# 03_CONNECTION.net
KiCad netlist of a schematic drawn in Altium Designer
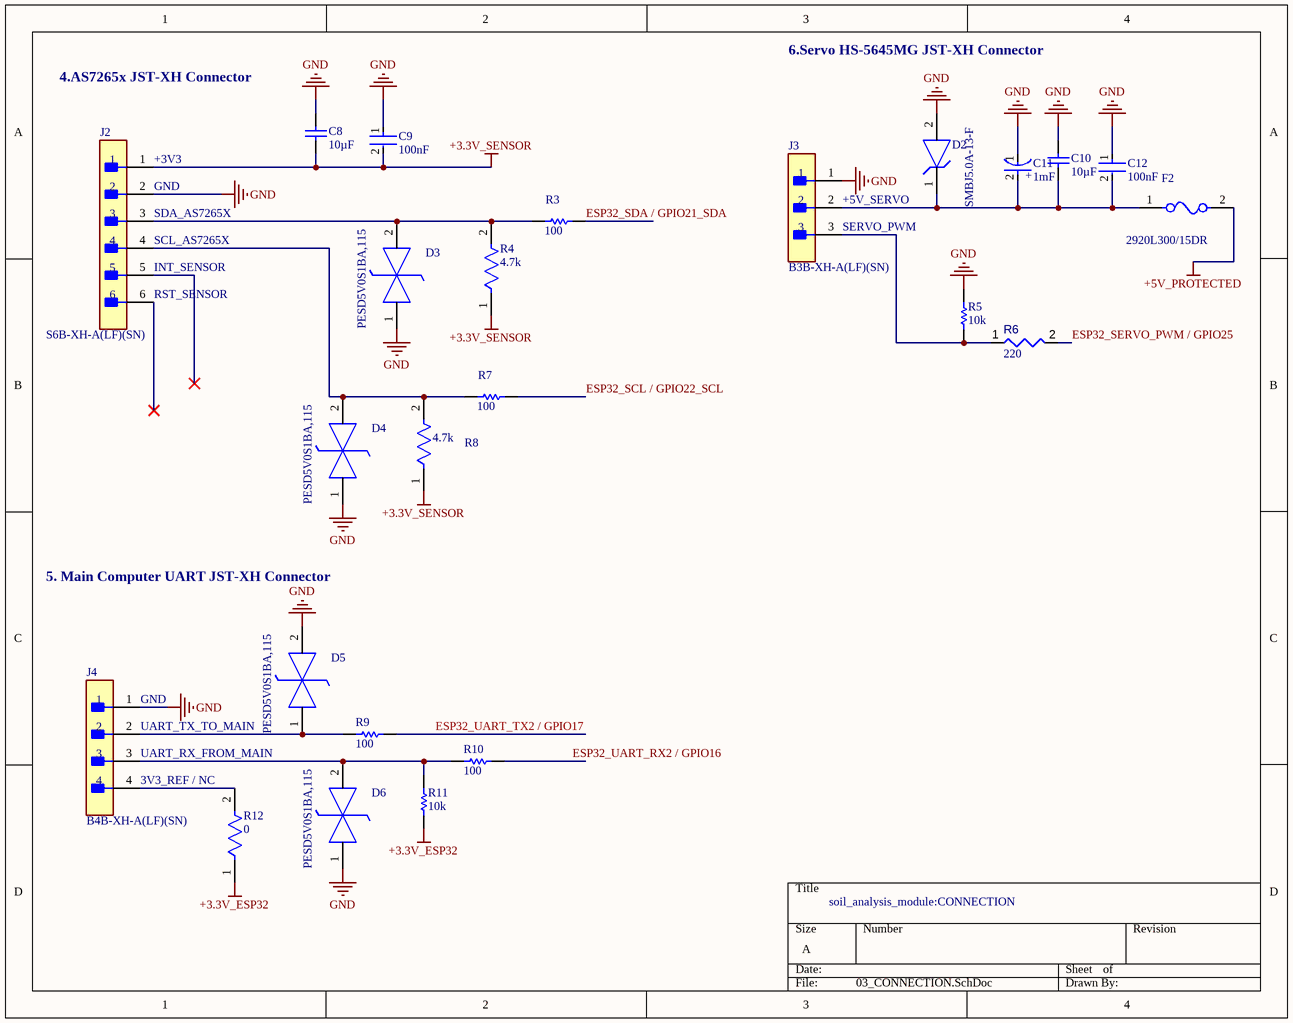
[diagram p0: 03_CONNECTION.SchDoc]

(export (version "E")
  (design (tool "Eeschema 10.0.6"))
  (components
    (comp (ref "C8")
      (value "10µF")
      (footprint "CAPC3216X180X55ML20T25")
      (description "16V 10uF X7R ±10% 1206 Multilayer Ceramic Capacitors MLCC - SMD/SMT ROHS")
      (fields (field (name "TOLERANCE") "10%") (field (name "Comment") "GRM31CR71C106KA12L"))
      (libsource (lib "Maksym Pleshyvtsev") (part "CAP-NP-2"))
    )
    (comp (ref "C9")
      (value "100nF")
      (footprint "FP-CC1206-1_25-MFG")
      (description "50V 100nF X7R ±10% 1206 Multilayer Ceramic Capacitors MLCC - SMD/SMT ROHS")
      (fields (field (name "TOLERANCE") "10%") (field (name "Comment") "CC1206KRX7R9BB104"))
      (libsource (lib "Maksym Pleshyvtsev") (part "11868f565c42a9108669ba33697ecf6"))
    )
    (comp (ref "C10")
      (value "10µF")
      (footprint "CAPC3216X180X55ML20T25")
      (description "16V 10uF X7R ±10% 1206 Multilayer Ceramic Capacitors MLCC - SMD/SMT ROHS")
      (fields (field (name "TOLERANCE") "10%") (field (name "Comment") "GRM31CR71C106KA12L"))
      (libsource (lib "Maksym Pleshyvtsev") (part "CAP-NP-2"))
    )
    (comp (ref "C11")
      (value "1mF")
      (footprint "FP-RAD-TH-D_8_0_5-L_15_1-MFG")
      (description "Aluminum Electrolytic Capacitor, 1000 uF, 10 V, ± 20%, 8000 hours @ 105°C, Radial Leaded")
      (fields (field (name "TOLERANCE") "20%") (field (name "Comment") "EEUFR1A102L"))
      (libsource (lib "Maksym Pleshyvtsev") (part "a00bbbee19879c290e62620ae7e47b1"))
    )
    (comp (ref "C12")
      (value "100nF")
      (footprint "FP-CC1206-1_25-MFG")
      (description "50V 100nF X7R ±10% 1206 Multilayer Ceramic Capacitors MLCC - SMD/SMT ROHS")
      (fields (field (name "TOLERANCE") "10%") (field (name "Comment") "CC1206KRX7R9BB104"))
      (libsource (lib "Maksym Pleshyvtsev") (part "11868f565c42a9108669ba33697ecf6"))
    )
    (comp (ref "D2")
      (value "SMBJ5.0A-13-F")
      (footprint "FP-SMB-MFG")
      (description "SMBJ5.0A Series 600 W 5.0 V Surface Mount Uni-Directional TVS Diode - DO-214AA")
      (libsource (lib "Maksym Pleshyvtsev") (part "673ecd2ea4d7fb87b4005b0cb348b7d"))
    )
    (comp (ref "D3")
      (value "PESD5V0S1BA,115")
      (footprint "PESD5V0S1BA,115-Footprint-1")
      (description "Tvs Diodes & Esd Suppressors; PESD5V0S1BA, 115; Nexperia; 5 V; 2; 14 V; 5.5 V")
      (libsource (lib "Maksym Pleshyvtsev") (part "PESD5V0S1BA,115-Symbol-1"))
    )
    (comp (ref "D4")
      (value "PESD5V0S1BA,115")
      (footprint "PESD5V0S1BA,115-Footprint-1")
      (description "Tvs Diodes & Esd Suppressors; PESD5V0S1BA, 115; Nexperia; 5 V; 2; 14 V; 5.5 V")
      (libsource (lib "Maksym Pleshyvtsev") (part "PESD5V0S1BA,115-Symbol-1"))
    )
    (comp (ref "D5")
      (value "PESD5V0S1BA,115")
      (footprint "PESD5V0S1BA,115-Footprint-1")
      (description "Tvs Diodes & Esd Suppressors; PESD5V0S1BA, 115; Nexperia; 5 V; 2; 14 V; 5.5 V")
      (libsource (lib "Maksym Pleshyvtsev") (part "PESD5V0S1BA,115-Symbol-1"))
    )
    (comp (ref "D6")
      (value "PESD5V0S1BA,115")
      (footprint "PESD5V0S1BA,115-Footprint-1")
      (description "Tvs Diodes & Esd Suppressors; PESD5V0S1BA, 115; Nexperia; 5 V; 2; 14 V; 5.5 V")
      (libsource (lib "Maksym Pleshyvtsev") (part "PESD5V0S1BA,115-Symbol-1"))
    )
    (comp (ref "F2")
      (value "2920L300/15DR")
      (footprint "FP-2920L-MFG")
      (description "PTC Resettable Fuses; 2920L300/15DR; LITTELFUSE; 5 A; 3 A; 20 s; 2920")
      (libsource (lib "Maksym Pleshyvtsev") (part "5bcf9b9f640e542cf0359d10258e979"))
    )
    (comp (ref "J2")
      (value "S6B-XH-A(LF)(SN)")
      (footprint "FP-S6B-XH-A_LF_SN-MFG")
      (description "Board Connector, 6 Contact(s), 1 Row(s), Male, Right Angle, Solder Terminal, ROHS COMPLIANT")
      (libsource (lib "Maksym Pleshyvtsev") (part "f2cb566baf1c37ab5a3b8e90bbeafd6"))
    )
    (comp (ref "J3")
      (value "B3B-XH-A(LF)(SN)")
      (footprint "FP-B3B-XH-A_LF_SN-MFG")
      (description "Connector Header, XH Series, 3 Position, 2.50mm, Through Hole, Press-Fit, Solder, Natural")
      (libsource (lib "Maksym Pleshyvtsev") (part "0d3f023dd272f625e17a2be33dea85f"))
    )
    (comp (ref "J4")
      (value "B4B-XH-A(LF)(SN)")
      (footprint "FP-B4B-XH-A_LF_SN-MFG")
      (description "Connector Header, 4 Positions, 2.50mm, Solder, Detent Lock, Natural")
      (libsource (lib "Maksym Pleshyvtsev") (part "299a8cea1bdcbc3624fe62c390fa72c"))
    )
    (comp (ref "R3")
      (value "100")
      (footprint "RESC3116X65X40LL10T20")
      (description "Res Thick Film 1206 100 Ohm 1% 0.25W(1/4W) ±100ppm/C Pad SMD T/R")
      (fields (field (name "TOLERANCE") "1%") (field (name "Comment") "RC1206FR-07100RL"))
      (libsource (lib "Maksym Pleshyvtsev") (part "RES-2"))
    )
    (comp (ref "R4")
      (value "4.7k")
      (footprint "FP-RC1206-0_65-MFG")
      (description "Res Thick Film 1206 4.7K Ohm 1% 0.25W(1/4W) ±100ppm/C Pad SMD T/R")
      (fields (field (name "TOLERANCE") "1%") (field (name "Comment") "RC1206FR-074K7L"))
      (libsource (lib "Maksym Pleshyvtsev") (part "1029c3af85768c4190bb7ad29bc67b5"))
    )
    (comp (ref "R5")
      (value "10k")
      (footprint "RESC3116X65X40ML10T20")
      (description "250Mw Thick Film Resistors 100Ppm/ 1% 10K 1206 Chip Resistor Surface Mount Rohs")
      (fields (field (name "TOLERANCE") "1%") (field (name "Comment") "RC1206FR-0710KL"))
      (libsource (lib "Maksym Pleshyvtsev") (part "RES-2"))
    )
    (comp (ref "R6")
      (value "220")
      (footprint "RC1206FR-07220RL-Footprint-1")
      (description "250mW Thick Film Resistors 200V ±100ppm/℃ ±1% 220Ω 1206 Chip Resistor - Surface Mount ROHS")
      (fields (field (name "TOLERANCE") "1%") (field (name "Comment") "RC1206FR-07220RL"))
      (libsource (lib "") (part "RES-2_1"))
    )
    (comp (ref "R7")
      (value "100")
      (footprint "RESC3116X65X40LL10T20")
      (description "Res Thick Film 1206 100 Ohm 1% 0.25W(1/4W) ±100ppm/C Pad SMD T/R")
      (fields (field (name "TOLERANCE") "1%") (field (name "Comment") "RC1206FR-07100RL"))
      (libsource (lib "Maksym Pleshyvtsev") (part "RES-2"))
    )
    (comp (ref "R8")
      (value "4.7k")
      (footprint "FP-RC1206-0_65-MFG")
      (description "Res Thick Film 1206 4.7K Ohm 1% 0.25W(1/4W) ±100ppm/C Pad SMD T/R")
      (fields (field (name "TOLERANCE") "1%") (field (name "Comment") "RC1206FR-074K7L"))
      (libsource (lib "Maksym Pleshyvtsev") (part "1029c3af85768c4190bb7ad29bc67b5"))
    )
    (comp (ref "R9")
      (value "100")
      (footprint "RESC3116X65X40LL10T20")
      (description "Res Thick Film 1206 100 Ohm 1% 0.25W(1/4W) ±100ppm/C Pad SMD T/R")
      (fields (field (name "TOLERANCE") "1%") (field (name "Comment") "RC1206FR-07100RL"))
      (libsource (lib "Maksym Pleshyvtsev") (part "RES-2"))
    )
    (comp (ref "R10")
      (value "100")
      (footprint "RESC3116X65X40LL10T20")
      (description "Res Thick Film 1206 100 Ohm 1% 0.25W(1/4W) ±100ppm/C Pad SMD T/R")
      (fields (field (name "TOLERANCE") "1%") (field (name "Comment") "RC1206FR-07100RL"))
      (libsource (lib "Maksym Pleshyvtsev") (part "RES-2"))
    )
    (comp (ref "R11")
      (value "10k")
      (footprint "RESC3116X65X40ML10T20")
      (description "250Mw Thick Film Resistors 100Ppm/ 1% 10K 1206 Chip Resistor Surface Mount Rohs")
      (fields (field (name "TOLERANCE") "1%") (field (name "Comment") "RC1206FR-0710KL"))
      (libsource (lib "Maksym Pleshyvtsev") (part "RES-2"))
    )
    (comp (ref "R12")
      (value "0")
      (footprint "FP-RC1206-MFG")
      (description "GENERAL PURPOSE CHIP RESISTOR Metal Glaze/thick Film, 0.25W, 0ohm, Surface Mount, 1206")
      (fields (field (name "TOLERANCE") "5%") (field (name "Comment") "RC1206JR-070RL"))
      (libsource (lib "Maksym Pleshyvtsev") (part "1029c3af85768c4190bb7ad29bc67b5"))
    )
  )
  (nets
    (net (code "1") (name "+3.3V_ESP32") (class "Default")
      (node (ref "R11") (pin "1") (pinfunction "1_1") (pintype "passive"))
      (node (ref "R12") (pin "1") (pinfunction "1_1") (pintype "passive"))
    )
    (net (code "2") (name "+3.3V_SENSOR") (class "Default")
      (node (ref "C8") (pin "1") (pinfunction "1_1") (pintype "passive"))
      (node (ref "C9") (pin "2") (pinfunction "2_2") (pintype "passive"))
      (node (ref "J2") (pin "1") (pinfunction "1_1") (pintype "passive"))
      (node (ref "R4") (pin "1") (pinfunction "1_1") (pintype "passive"))
      (node (ref "R8") (pin "1") (pinfunction "1_1") (pintype "passive"))
    )
    (net (code "3") (name "+5V_PROTECTED") (class "Default")
      (node (ref "F2") (pin "2") (pinfunction "2_2") (pintype "passive"))
    )
    (net (code "4") (name "/ESP32_SCL {slash} GPIO22_SCL") (class "Default")
      (node (ref "R7") (pin "2") (pinfunction "2_2") (pintype "passive"))
    )
    (net (code "5") (name "/ESP32_SDA {slash} GPIO21_SDA") (class "Default")
      (node (ref "R3") (pin "2") (pinfunction "2_2") (pintype "passive"))
    )
    (net (code "6") (name "/ESP32_SERVO_PWM {slash} GPIO25") (class "Default")
      (node (ref "R6") (pin "2") (pinfunction "2_2") (pintype "passive"))
    )
    (net (code "7") (name "/ESP32_UART_RX2 {slash} GPIO16") (class "Default")
      (node (ref "R10") (pin "2") (pinfunction "2_2") (pintype "passive"))
    )
    (net (code "8") (name "/ESP32_UART_TX2 {slash} GPIO17") (class "Default")
      (node (ref "R9") (pin "2") (pinfunction "2_2") (pintype "passive"))
    )
    (net (code "9") (name "GND") (class "Default")
      (node (ref "C10") (pin "2") (pinfunction "2_2") (pintype "passive"))
      (node (ref "C11") (pin "1") (pinfunction "C_1") (pintype "passive"))
      (node (ref "C12") (pin "1") (pinfunction "1_1") (pintype "passive"))
      (node (ref "C8") (pin "2") (pinfunction "2_2") (pintype "passive"))
      (node (ref "C9") (pin "1") (pinfunction "1_1") (pintype "passive"))
      (node (ref "D2") (pin "2") (pinfunction "A_2") (pintype "passive"))
      (node (ref "D3") (pin "1") (pinfunction "K1_1") (pintype "passive"))
      (node (ref "D4") (pin "1") (pinfunction "K1_1") (pintype "passive"))
      (node (ref "D5") (pin "2") (pinfunction "K2_2") (pintype "passive"))
      (node (ref "D6") (pin "1") (pinfunction "K1_1") (pintype "passive"))
      (node (ref "J2") (pin "2") (pinfunction "2_2") (pintype "passive"))
      (node (ref "J3") (pin "1") (pinfunction "1_1") (pintype "passive"))
      (node (ref "J4") (pin "1") (pinfunction "1_1") (pintype "passive"))
      (node (ref "R5") (pin "2") (pinfunction "2_2") (pintype "passive"))
    )
    (net (code "10") (name "Net-(C11-A)") (class "Default")
      (node (ref "C10") (pin "1") (pinfunction "1_1") (pintype "passive"))
      (node (ref "C11") (pin "2") (pinfunction "A_2") (pintype "passive"))
      (node (ref "C12") (pin "2") (pinfunction "2_2") (pintype "passive"))
      (node (ref "D2") (pin "1") (pinfunction "C_1") (pintype "passive"))
      (node (ref "F2") (pin "1") (pinfunction "1_1") (pintype "passive"))
      (node (ref "J3") (pin "2") (pinfunction "2_2") (pintype "passive"))
    )
    (net (code "11") (name "Net-(D3-K2)") (class "Default")
      (node (ref "D3") (pin "2") (pinfunction "K2_2") (pintype "passive"))
      (node (ref "J2") (pin "3") (pinfunction "3_3") (pintype "passive"))
      (node (ref "R3") (pin "1") (pinfunction "1_1") (pintype "passive"))
      (node (ref "R4") (pin "2") (pinfunction "2_2") (pintype "passive"))
    )
    (net (code "12") (name "Net-(D4-K2)") (class "Default")
      (node (ref "D4") (pin "2") (pinfunction "K2_2") (pintype "passive"))
      (node (ref "J2") (pin "4") (pinfunction "4_4") (pintype "passive"))
      (node (ref "R7") (pin "1") (pinfunction "1_1") (pintype "passive"))
      (node (ref "R8") (pin "2") (pinfunction "2_2") (pintype "passive"))
    )
    (net (code "13") (name "Net-(D5-K1)") (class "Default")
      (node (ref "D5") (pin "1") (pinfunction "K1_1") (pintype "passive"))
      (node (ref "J4") (pin "2") (pinfunction "2_2") (pintype "passive"))
      (node (ref "R9") (pin "1") (pinfunction "1_1") (pintype "passive"))
    )
    (net (code "14") (name "Net-(D6-K2)") (class "Default")
      (node (ref "D6") (pin "2") (pinfunction "K2_2") (pintype "passive"))
      (node (ref "J4") (pin "3") (pinfunction "3_3") (pintype "passive"))
      (node (ref "R10") (pin "1") (pinfunction "1_1") (pintype "passive"))
      (node (ref "R11") (pin "2") (pinfunction "2_2") (pintype "passive"))
    )
    (net (code "15") (name "Net-(J3-Pad3)") (class "Default")
      (node (ref "J3") (pin "3") (pinfunction "3_3") (pintype "passive"))
      (node (ref "R5") (pin "1") (pinfunction "1_1") (pintype "passive"))
      (node (ref "R6") (pin "1") (pinfunction "1_1") (pintype "passive"))
    )
    (net (code "16") (name "Net-(J4-Pad4)") (class "Default")
      (node (ref "J4") (pin "4") (pinfunction "4_4") (pintype "passive"))
      (node (ref "R12") (pin "2") (pinfunction "2_2") (pintype "passive"))
    )
    (net (code "17") (name "unconnected-(J2-Pad5)") (class "Default")
      (node (ref "J2") (pin "5") (pinfunction "5_5") (pintype "passive+no_connect"))
    )
    (net (code "18") (name "unconnected-(J2-Pad6)") (class "Default")
      (node (ref "J2") (pin "6") (pinfunction "6_6") (pintype "passive+no_connect"))
    )
  )
)
